# dc26-dev-board.net
KiCad netlist of a schematic drawn in EAGLE
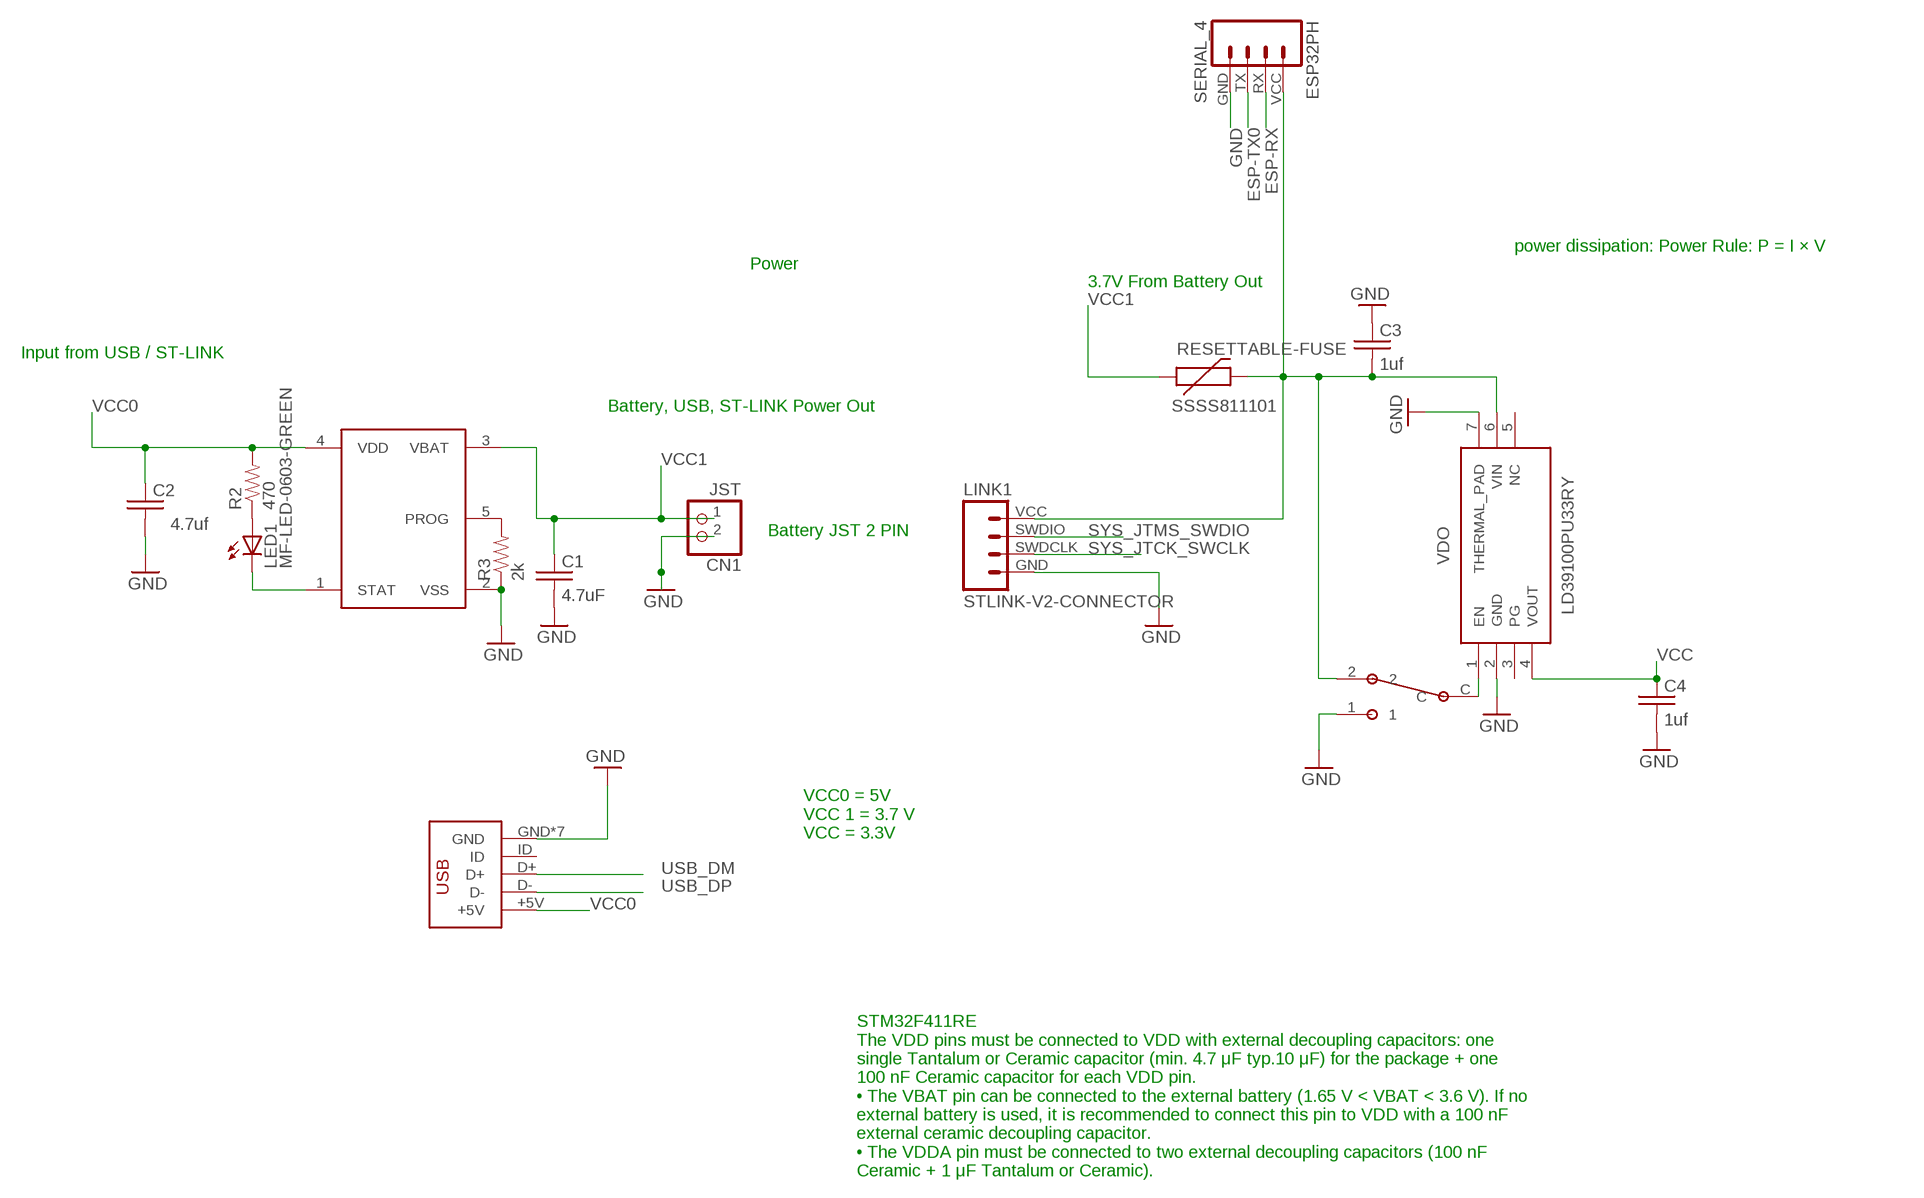
[diagram p0: schematic, sheet 1]
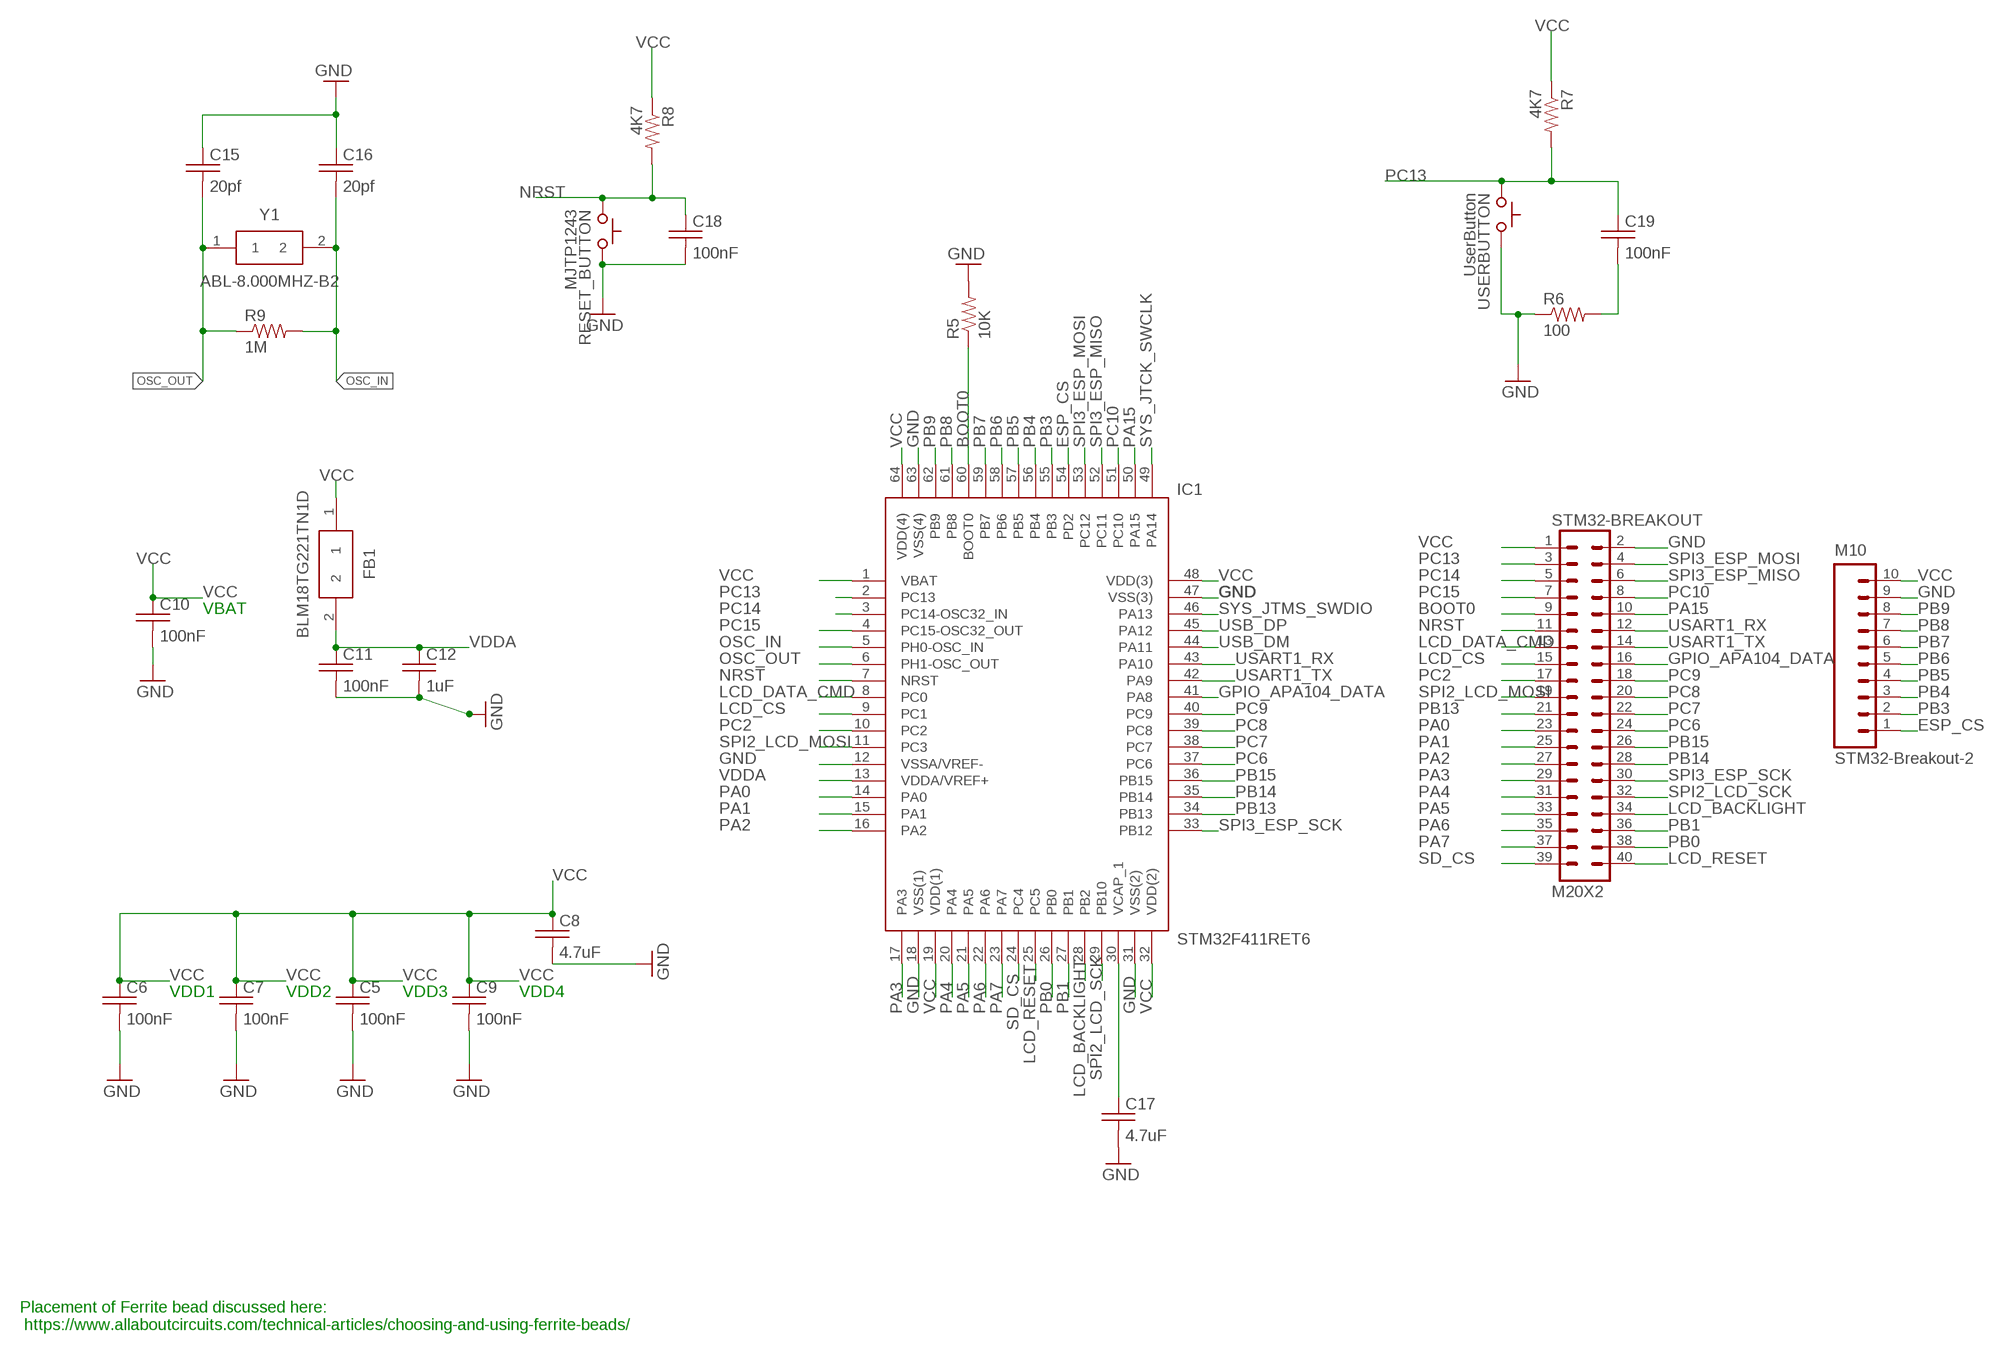
[diagram p1: schematic, sheet 2]
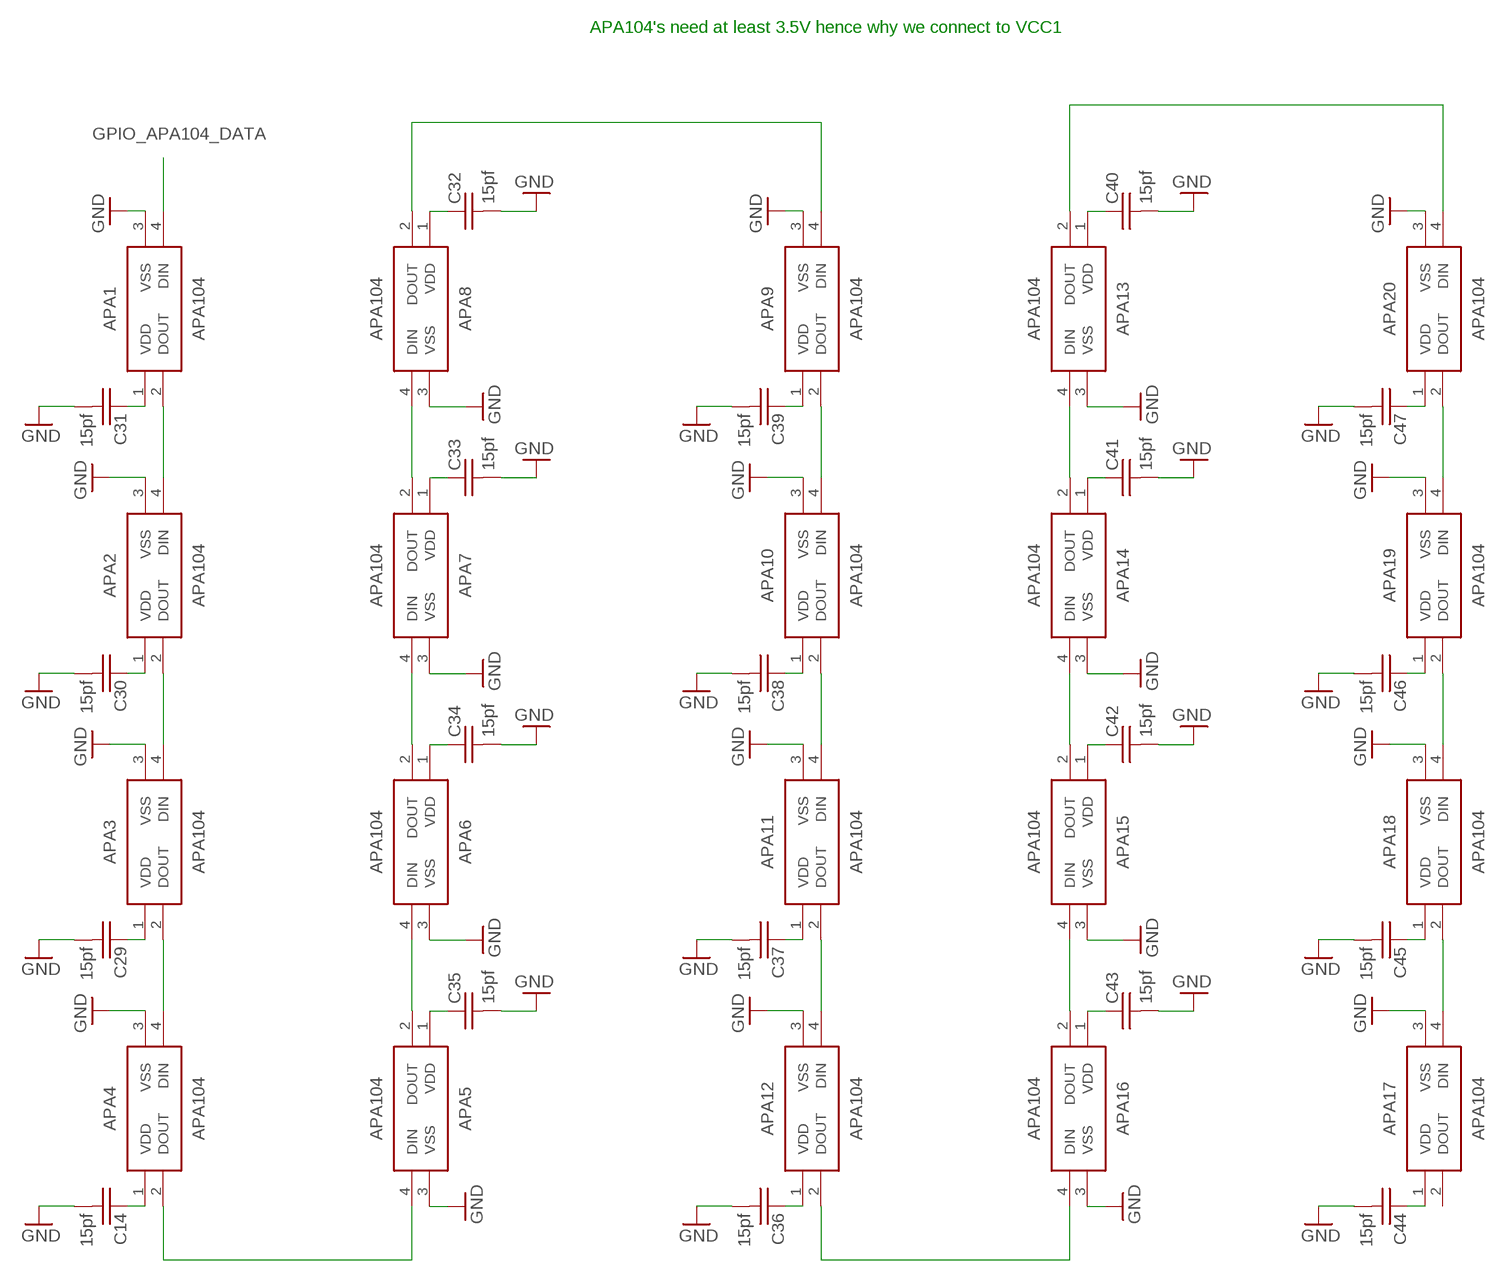
[diagram p2: schematic, sheet 3]
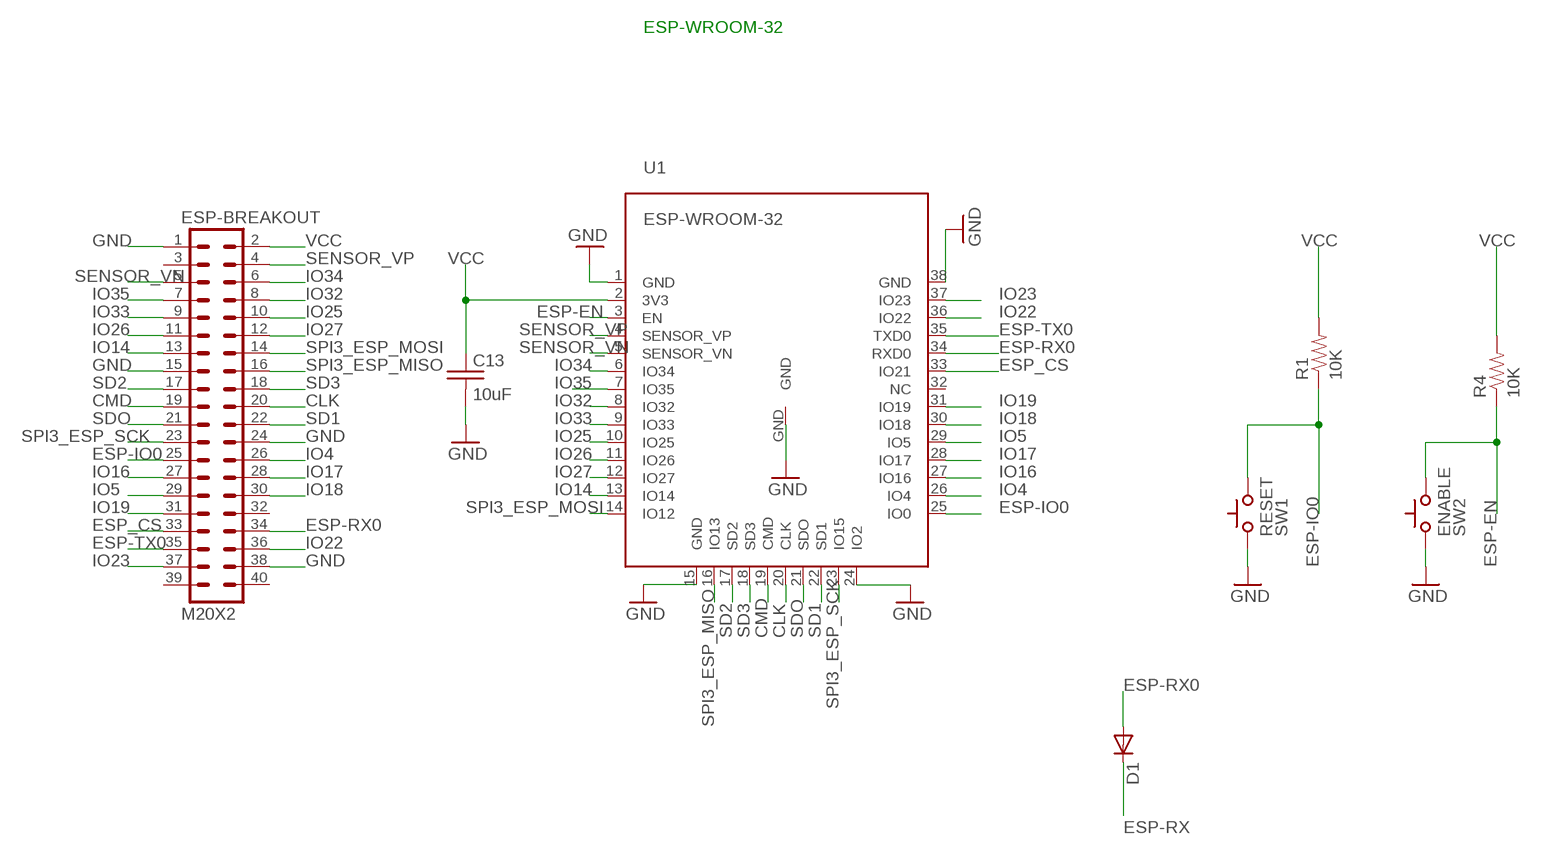
[diagram p3: schematic, sheet 4]
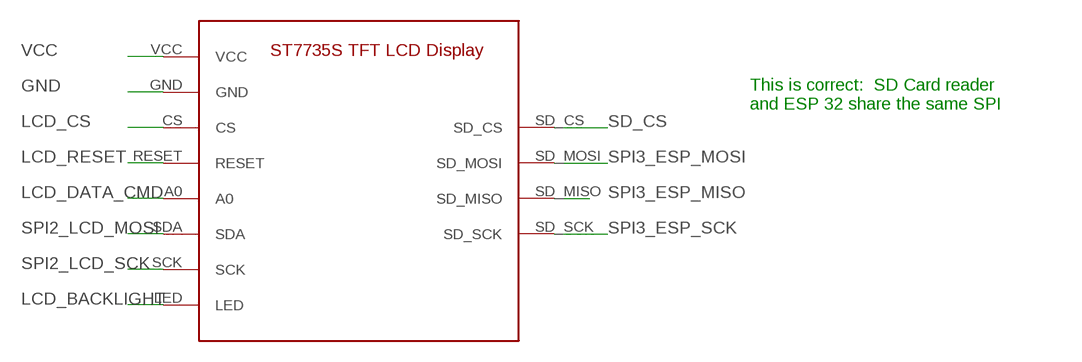
[diagram p4: schematic, sheet 5]
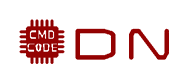
[diagram p5: schematic, sheet 6]
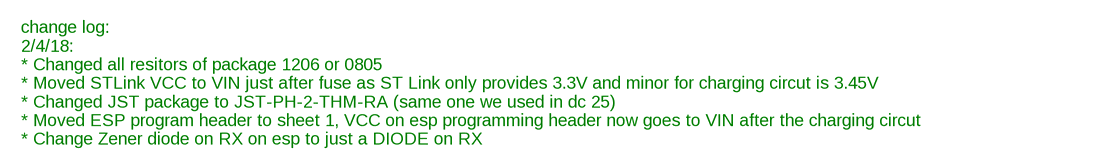
[diagram p6: schematic, sheet 7]

(export (version "E")
  (design (tool "Eeschema 10.0.6"))
  (components
    (comp (ref "C5")
      (value "100nF")
      (footprint "eagle-import:C0805")
      (libsource (lib "eagle-import") (part "C-USC0805"))
    )
    (comp (ref "C6")
      (value "100nF")
      (footprint "eagle-import:C0805")
      (libsource (lib "eagle-import") (part "C-USC0805"))
    )
    (comp (ref "C7")
      (value "100nF")
      (footprint "eagle-import:C0805")
      (libsource (lib "eagle-import") (part "C-USC0805"))
    )
    (comp (ref "C8")
      (value "4.7uF")
      (footprint "eagle-import:C0805")
      (libsource (lib "eagle-import") (part "C-USC0805"))
    )
    (comp (ref "C9")
      (value "100nF")
      (footprint "eagle-import:C0805")
      (libsource (lib "eagle-import") (part "C-USC0805"))
    )
    (comp (ref "C10")
      (value "100nF")
      (footprint "eagle-import:C0805")
      (libsource (lib "eagle-import") (part "C-USC0805"))
    )
    (comp (ref "C11")
      (value "100nF")
      (footprint "eagle-import:C0805")
      (libsource (lib "eagle-import") (part "C-USC0805"))
    )
    (comp (ref "C12")
      (value "1uF")
      (footprint "eagle-import:C0805")
      (libsource (lib "eagle-import") (part "C-USC0805"))
    )
    (comp (ref "C15")
      (value "20pf")
      (footprint "eagle-import:C0805")
      (libsource (lib "eagle-import") (part "C-USC0805"))
    )
    (comp (ref "C16")
      (value "20pf")
      (footprint "eagle-import:C0805")
      (libsource (lib "eagle-import") (part "C-USC0805"))
    )
    (comp (ref "C17")
      (value "4.7uF")
      (footprint "eagle-import:C0805")
      (libsource (lib "eagle-import") (part "C-USC0805"))
    )
    (comp (ref "C18")
      (value "100nF")
      (footprint "eagle-import:C0805")
      (libsource (lib "eagle-import") (part "C-USC0805"))
    )
    (comp (ref "C19")
      (value "100nF")
      (footprint "eagle-import:C0805")
      (libsource (lib "eagle-import") (part "C-USC0805"))
    )
    (comp (ref "FB1")
      (value "BLM18TG221TN1D")
      (footprint "eagle-import:BEADC1608X75N")
      (fields (field (name "RS_PART_NUMBER") "6197526"))
      (libsource (lib "eagle-import") (part "BLM18TG221TN1D"))
    )
    (comp (ref "IC1")
      (value "STM32F411RET6")
      (footprint "eagle-import:QFP50P1200X1200X160-64N")
      (fields (field (name "RS_PART_NUMBER") "1106617P"))
      (libsource (lib "eagle-import") (part "STM32F411RET6"))
    )
    (comp (ref "M10")
      (value "STM32-Breakout-2")
      (footprint "eagle-import:1X10")
      (libsource (lib "eagle-import") (part "M10SILK_FEMALE_PTH"))
    )
    (comp (ref "R5")
      (value "10K")
      (footprint "eagle-import:0805")
      (libsource (lib "eagle-import") (part "RESISTOR0805-RES"))
    )
    (comp (ref "R6")
      (value "100")
      (footprint "eagle-import:0805")
      (libsource (lib "eagle-import") (part "RESISTOR0805-RES"))
    )
    (comp (ref "R7")
      (value "4K7")
      (footprint "eagle-import:0805")
      (libsource (lib "eagle-import") (part "RESISTOR0805-RES"))
    )
    (comp (ref "R8")
      (value "4K7")
      (footprint "eagle-import:0805")
      (libsource (lib "eagle-import") (part "RESISTOR0805-RES"))
    )
    (comp (ref "R9")
      (value "1M")
      (footprint "eagle-import:0805")
      (libsource (lib "eagle-import") (part "RESISTOR0805-RES"))
    )
    (comp (ref "RESET_BUTTON")
      (value "MJTP1243")
      (footprint "eagle-import:TACTILE-2PIN-NARROW")
      (libsource (lib "eagle-import") (part "SWITCH_TACTILETACTILE-2PIN-NARROW"))
    )
    (comp (ref "STM32-BREAKOUT")
      (value "M20X2")
      (footprint "eagle-import:2X20")
      (libsource (lib "eagle-import") (part "M20X2"))
    )
    (comp (ref "USERBUTTON")
      (value "UserButton")
      (footprint "eagle-import:TACTILE-2PIN-NARROW")
      (libsource (lib "eagle-import") (part "SWITCH_TACTILETACTILE-2PIN-NARROW"))
    )
    (comp (ref "Y1")
      (value "ABL-8.000MHZ-B2")
      (footprint "eagle-import:HC_49US_(AT49)PTH")
      (libsource (lib "eagle-import") (part "ABL-8.000MHZ-B2"))
    )
    (comp (ref "C13")
      (value "10uF")
      (footprint "eagle-import:C0805")
      (libsource (lib "eagle-import") (part "C-USC0805"))
    )
    (comp (ref "D1")
      (value "DIODESOD")
      (footprint "eagle-import:SOD-323")
      (libsource (lib "eagle-import") (part "DIODESOD"))
    )
    (comp (ref "ENABLE")
      (value "SW2")
      (footprint "eagle-import:TACTILE-2PIN-NARROW")
      (libsource (lib "eagle-import") (part "SWITCH_TACTILETACTILE-2PIN-NARROW"))
    )
    (comp (ref "ESP-BREAKOUT")
      (value "M20X2")
      (footprint "eagle-import:2X20")
      (libsource (lib "eagle-import") (part "M20X2"))
    )
    (comp (ref "R1")
      (value "10K")
      (footprint "eagle-import:0805")
      (libsource (lib "eagle-import") (part "RESISTOR0805-RES"))
    )
    (comp (ref "R4")
      (value "10K")
      (footprint "eagle-import:0805")
      (libsource (lib "eagle-import") (part "RESISTOR0805-RES"))
    )
    (comp (ref "RESET")
      (value "SW1")
      (footprint "eagle-import:TACTILE-2PIN-NARROW")
      (libsource (lib "eagle-import") (part "SWITCH_TACTILETACTILE-2PIN-NARROW"))
    )
    (comp (ref "U1")
      (value "ESP-WROOM-32")
      (footprint "eagle-import:ESP-WROOM-32")
      (libsource (lib "eagle-import") (part "ESP-WROOM-32"))
    )
    (comp (ref "C1")
      (value "4.7uF")
      (footprint "eagle-import:C0805")
      (libsource (lib "eagle-import") (part "C-USC0805"))
    )
    (comp (ref "C2")
      (value "4.7uf")
      (footprint "eagle-import:C0805")
      (libsource (lib "eagle-import") (part "C-USC0805"))
    )
    (comp (ref "C3")
      (value "1uf")
      (footprint "eagle-import:C0805")
      (libsource (lib "eagle-import") (part "C-USC0805"))
    )
    (comp (ref "C4")
      (value "1uf")
      (footprint "eagle-import:C0805")
      (libsource (lib "eagle-import") (part "C-USC0805"))
    )
    (comp (ref "CHARGING_CIRCUT")
      (value "MCP73831")
      (footprint "eagle-import:SOT23-5")
      (libsource (lib "eagle-import") (part "DS21984E"))
    )
    (comp (ref "CN1")
      (value "JST")
      (footprint "eagle-import:JST-PH-2-THM-RA")
      (libsource (lib "eagle-import") (part "JST_2PIN-THM-RA"))
    )
    (comp (ref "ESP32PH")
      (value "SERIAL_4")
      (footprint "eagle-import:SERIAL_HEADER_4")
      (libsource (lib "eagle-import") (part "SERIAL_4"))
    )
    (comp (ref "LED1")
      (value "MF-LED-0603-GREEN")
      (footprint "eagle-import:LED-1206")
      (libsource (lib "eagle-import") (part "LED1206"))
    )
    (comp (ref "LINK1")
      (value "STLINK-V2-CONNECTOR")
      (footprint "eagle-import:1X04")
      (libsource (lib "eagle-import") (part "STLINK-V2-CONNECTOR"))
    )
    (comp (ref "P1")
      (value "SSSS811101")
      (footprint "eagle-import:SPDT_SSAJ120100")
      (libsource (lib "eagle-import") (part "SWITCH_SPDT"))
    )
    (comp (ref "R2")
      (value "470")
      (footprint "eagle-import:0805")
      (libsource (lib "eagle-import") (part "RESISTOR0805-RES"))
    )
    (comp (ref "R3")
      (value "2k")
      (footprint "eagle-import:0805")
      (libsource (lib "eagle-import") (part "RESISTOR0805-RES"))
    )
    (comp (ref "RESETTABLE-FUSE")
      (value "SSSS811101")
      (footprint "eagle-import:PTC-1206")
      (libsource (lib "eagle-import") (part "PTCSMD"))
    )
    (comp (ref "USB")
      (value "DX4R005JJ2DX4R005JJ2")
      (footprint "eagle-import:DX4R005JJ2")
      (libsource (lib "eagle-import") (part "DX4R005JJ2DX4R005JJ2"))
    )
    (comp (ref "VDO")
      (value "LD39100PU33RY")
      (footprint "eagle-import:SON95P300X300X90-7N")
      (libsource (lib "eagle-import") (part "LD39100PU33RY"))
    )
    (comp (ref "U$1")
      (value "ST7735S_LCD_MODULE")
      (footprint "eagle-import:ST7735S_LCD_DISPLAY")
      (libsource (lib "eagle-import") (part "ST7735S_LCD_MODULE"))
    )
    (comp (ref "U$2")
      (value "CMD_C0DE_LOGO")
      (footprint "eagle-import:CMD_C0DE_LOGO")
      (libsource (lib "eagle-import") (part "CMD_C0DE_LOGO"))
    )
    (comp (ref "U$3")
      (value "DARKNET_DD")
      (footprint "eagle-import:DARKNET_D")
      (libsource (lib "eagle-import") (part "DARKNET_DD"))
    )
    (comp (ref "U$4")
      (value "DARKNET_NN")
      (footprint "eagle-import:DARKNET_N")
      (libsource (lib "eagle-import") (part "DARKNET_NN"))
    )
    (comp (ref "APA1")
      (value "APA104")
      (footprint "eagle-import:APA104")
      (libsource (lib "eagle-import") (part "APA104"))
    )
    (comp (ref "APA2")
      (value "APA104")
      (footprint "eagle-import:APA104")
      (libsource (lib "eagle-import") (part "APA104"))
    )
    (comp (ref "APA3")
      (value "APA104")
      (footprint "eagle-import:APA104")
      (libsource (lib "eagle-import") (part "APA104"))
    )
    (comp (ref "APA4")
      (value "APA104")
      (footprint "eagle-import:APA104")
      (libsource (lib "eagle-import") (part "APA104"))
    )
    (comp (ref "APA5")
      (value "APA104")
      (footprint "eagle-import:APA104")
      (libsource (lib "eagle-import") (part "APA104"))
    )
    (comp (ref "APA6")
      (value "APA104")
      (footprint "eagle-import:APA104")
      (libsource (lib "eagle-import") (part "APA104"))
    )
    (comp (ref "APA7")
      (value "APA104")
      (footprint "eagle-import:APA104")
      (libsource (lib "eagle-import") (part "APA104"))
    )
    (comp (ref "APA8")
      (value "APA104")
      (footprint "eagle-import:APA104")
      (libsource (lib "eagle-import") (part "APA104"))
    )
    (comp (ref "APA9")
      (value "APA104")
      (footprint "eagle-import:APA104")
      (libsource (lib "eagle-import") (part "APA104"))
    )
    (comp (ref "APA10")
      (value "APA104")
      (footprint "eagle-import:APA104")
      (libsource (lib "eagle-import") (part "APA104"))
    )
    (comp (ref "APA11")
      (value "APA104")
      (footprint "eagle-import:APA104")
      (libsource (lib "eagle-import") (part "APA104"))
    )
    (comp (ref "APA12")
      (value "APA104")
      (footprint "eagle-import:APA104")
      (libsource (lib "eagle-import") (part "APA104"))
    )
    (comp (ref "APA13")
      (value "APA104")
      (footprint "eagle-import:APA104")
      (libsource (lib "eagle-import") (part "APA104"))
    )
    (comp (ref "APA14")
      (value "APA104")
      (footprint "eagle-import:APA104")
      (libsource (lib "eagle-import") (part "APA104"))
    )
    (comp (ref "APA15")
      (value "APA104")
      (footprint "eagle-import:APA104")
      (libsource (lib "eagle-import") (part "APA104"))
    )
    (comp (ref "APA16")
      (value "APA104")
      (footprint "eagle-import:APA104")
      (libsource (lib "eagle-import") (part "APA104"))
    )
    (comp (ref "APA17")
      (value "APA104")
      (footprint "eagle-import:APA104")
      (libsource (lib "eagle-import") (part "APA104"))
    )
    (comp (ref "APA18")
      (value "APA104")
      (footprint "eagle-import:APA104")
      (libsource (lib "eagle-import") (part "APA104"))
    )
    (comp (ref "APA19")
      (value "APA104")
      (footprint "eagle-import:APA104")
      (libsource (lib "eagle-import") (part "APA104"))
    )
    (comp (ref "APA20")
      (value "APA104")
      (footprint "eagle-import:APA104")
      (libsource (lib "eagle-import") (part "APA104"))
    )
    (comp (ref "C14")
      (value "15pf")
      (footprint "eagle-import:C0805")
      (libsource (lib "eagle-import") (part "C-USC0805"))
    )
    (comp (ref "C29")
      (value "15pf")
      (footprint "eagle-import:C0805")
      (libsource (lib "eagle-import") (part "C-USC0805"))
    )
    (comp (ref "C30")
      (value "15pf")
      (footprint "eagle-import:C0805")
      (libsource (lib "eagle-import") (part "C-USC0805"))
    )
    (comp (ref "C31")
      (value "15pf")
      (footprint "eagle-import:C0805")
      (libsource (lib "eagle-import") (part "C-USC0805"))
    )
    (comp (ref "C32")
      (value "15pf")
      (footprint "eagle-import:C0805")
      (libsource (lib "eagle-import") (part "C-USC0805"))
    )
    (comp (ref "C33")
      (value "15pf")
      (footprint "eagle-import:C0805")
      (libsource (lib "eagle-import") (part "C-USC0805"))
    )
    (comp (ref "C34")
      (value "15pf")
      (footprint "eagle-import:C0805")
      (libsource (lib "eagle-import") (part "C-USC0805"))
    )
    (comp (ref "C35")
      (value "15pf")
      (footprint "eagle-import:C0805")
      (libsource (lib "eagle-import") (part "C-USC0805"))
    )
    (comp (ref "C36")
      (value "15pf")
      (footprint "eagle-import:C0805")
      (libsource (lib "eagle-import") (part "C-USC0805"))
    )
    (comp (ref "C37")
      (value "15pf")
      (footprint "eagle-import:C0805")
      (libsource (lib "eagle-import") (part "C-USC0805"))
    )
    (comp (ref "C38")
      (value "15pf")
      (footprint "eagle-import:C0805")
      (libsource (lib "eagle-import") (part "C-USC0805"))
    )
    (comp (ref "C39")
      (value "15pf")
      (footprint "eagle-import:C0805")
      (libsource (lib "eagle-import") (part "C-USC0805"))
    )
    (comp (ref "C40")
      (value "15pf")
      (footprint "eagle-import:C0805")
      (libsource (lib "eagle-import") (part "C-USC0805"))
    )
    (comp (ref "C41")
      (value "15pf")
      (footprint "eagle-import:C0805")
      (libsource (lib "eagle-import") (part "C-USC0805"))
    )
    (comp (ref "C42")
      (value "15pf")
      (footprint "eagle-import:C0805")
      (libsource (lib "eagle-import") (part "C-USC0805"))
    )
    (comp (ref "C43")
      (value "15pf")
      (footprint "eagle-import:C0805")
      (libsource (lib "eagle-import") (part "C-USC0805"))
    )
    (comp (ref "C44")
      (value "15pf")
      (footprint "eagle-import:C0805")
      (libsource (lib "eagle-import") (part "C-USC0805"))
    )
    (comp (ref "C45")
      (value "15pf")
      (footprint "eagle-import:C0805")
      (libsource (lib "eagle-import") (part "C-USC0805"))
    )
    (comp (ref "C46")
      (value "15pf")
      (footprint "eagle-import:C0805")
      (libsource (lib "eagle-import") (part "C-USC0805"))
    )
    (comp (ref "C47")
      (value "15pf")
      (footprint "eagle-import:C0805")
      (libsource (lib "eagle-import") (part "C-USC0805"))
    )
  )
  (nets
    (net (code "1") (name "BOOT0") (class "Default")
      (node (ref "IC1") (pin "60") (pinfunction "BOOT0_60") (pintype "passive"))
      (node (ref "R5") (pin "1") (pinfunction "1_1") (pintype "passive"))
      (node (ref "STM32-BREAKOUT") (pin "9") (pinfunction "9_9") (pintype "passive"))
    )
    (net (code "2") (name "CLK") (class "Default")
      (node (ref "ESP-BREAKOUT") (pin "20") (pinfunction "20_20") (pintype "passive"))
      (node (ref "U1") (pin "20") (pinfunction "CLK_20") (pintype "bidirectional"))
    )
    (net (code "3") (name "CMD") (class "Default")
      (node (ref "ESP-BREAKOUT") (pin "19") (pinfunction "19_19") (pintype "passive"))
      (node (ref "U1") (pin "19") (pinfunction "CMD_19") (pintype "bidirectional"))
    )
    (net (code "4") (name "ESP-EN") (class "Default")
      (node (ref "ENABLE") (pin "P$1") (pinfunction "A_P$1") (pintype "passive"))
      (node (ref "R4") (pin "1") (pinfunction "1_1") (pintype "passive"))
      (node (ref "U1") (pin "3") (pinfunction "EN_3") (pintype "bidirectional"))
    )
    (net (code "5") (name "ESP-IO0") (class "Default")
      (node (ref "ESP-BREAKOUT") (pin "25") (pinfunction "25_25") (pintype "passive"))
      (node (ref "R1") (pin "1") (pinfunction "1_1") (pintype "passive"))
      (node (ref "RESET") (pin "P$1") (pinfunction "A_P$1") (pintype "passive"))
      (node (ref "U1") (pin "25") (pinfunction "IO0_25") (pintype "bidirectional"))
    )
    (net (code "6") (name "ESP-RX") (class "Default")
      (node (ref "D1") (pin "1") (pinfunction "C_1") (pintype "passive"))
      (node (ref "ESP32PH") (pin "RX") (pinfunction "RX_RX") (pintype "bidirectional"))
    )
    (net (code "7") (name "ESP-RX0") (class "Default")
      (node (ref "D1") (pin "2") (pinfunction "A_2") (pintype "passive"))
      (node (ref "ESP-BREAKOUT") (pin "34") (pinfunction "34_34") (pintype "passive"))
      (node (ref "U1") (pin "34") (pinfunction "RXD0_34") (pintype "bidirectional"))
    )
    (net (code "8") (name "ESP-TX0") (class "Default")
      (node (ref "ESP-BREAKOUT") (pin "35") (pinfunction "35_35") (pintype "passive"))
      (node (ref "ESP32PH") (pin "TX") (pinfunction "TX_TX") (pintype "input"))
      (node (ref "U1") (pin "35") (pinfunction "TXD0_35") (pintype "bidirectional"))
    )
    (net (code "9") (name "ESP_CS") (class "Default")
      (node (ref "ESP-BREAKOUT") (pin "33") (pinfunction "33_33") (pintype "passive"))
      (node (ref "IC1") (pin "54") (pinfunction "PD2_54") (pintype "passive"))
      (node (ref "M10") (pin "1") (pinfunction "1_1") (pintype "passive"))
      (node (ref "U1") (pin "33") (pinfunction "IO21_33") (pintype "bidirectional"))
    )
    (net (code "10") (name "GND") (class "Default")
      (node (ref "APA1") (pin "3") (pinfunction "VSS_3") (pintype "power_in"))
      (node (ref "APA10") (pin "3") (pinfunction "VSS_3") (pintype "power_in"))
      (node (ref "APA11") (pin "3") (pinfunction "VSS_3") (pintype "power_in"))
      (node (ref "APA12") (pin "3") (pinfunction "VSS_3") (pintype "power_in"))
      (node (ref "APA13") (pin "3") (pinfunction "VSS_3") (pintype "power_in"))
      (node (ref "APA14") (pin "3") (pinfunction "VSS_3") (pintype "power_in"))
      (node (ref "APA15") (pin "3") (pinfunction "VSS_3") (pintype "power_in"))
      (node (ref "APA16") (pin "3") (pinfunction "VSS_3") (pintype "power_in"))
      (node (ref "APA17") (pin "3") (pinfunction "VSS_3") (pintype "power_in"))
      (node (ref "APA18") (pin "3") (pinfunction "VSS_3") (pintype "power_in"))
      (node (ref "APA19") (pin "3") (pinfunction "VSS_3") (pintype "power_in"))
      (node (ref "APA2") (pin "3") (pinfunction "VSS_3") (pintype "power_in"))
      (node (ref "APA20") (pin "3") (pinfunction "VSS_3") (pintype "power_in"))
      (node (ref "APA3") (pin "3") (pinfunction "VSS_3") (pintype "power_in"))
      (node (ref "APA4") (pin "3") (pinfunction "VSS_3") (pintype "power_in"))
      (node (ref "APA5") (pin "3") (pinfunction "VSS_3") (pintype "power_in"))
      (node (ref "APA6") (pin "3") (pinfunction "VSS_3") (pintype "power_in"))
      (node (ref "APA7") (pin "3") (pinfunction "VSS_3") (pintype "power_in"))
      (node (ref "APA8") (pin "3") (pinfunction "VSS_3") (pintype "power_in"))
      (node (ref "APA9") (pin "3") (pinfunction "VSS_3") (pintype "power_in"))
      (node (ref "C1") (pin "2") (pinfunction "2_2") (pintype "passive"))
      (node (ref "C10") (pin "2") (pinfunction "2_2") (pintype "passive"))
      (node (ref "C11") (pin "2") (pinfunction "2_2") (pintype "passive"))
      (node (ref "C12") (pin "2") (pinfunction "2_2") (pintype "passive"))
      (node (ref "C13") (pin "2") (pinfunction "2_2") (pintype "passive"))
      (node (ref "C14") (pin "2") (pinfunction "2_2") (pintype "passive"))
      (node (ref "C15") (pin "1") (pinfunction "1_1") (pintype "passive"))
      (node (ref "C16") (pin "1") (pinfunction "1_1") (pintype "passive"))
      (node (ref "C17") (pin "2") (pinfunction "2_2") (pintype "passive"))
      (node (ref "C18") (pin "2") (pinfunction "2_2") (pintype "passive"))
      (node (ref "C2") (pin "2") (pinfunction "2_2") (pintype "passive"))
      (node (ref "C29") (pin "2") (pinfunction "2_2") (pintype "passive"))
      (node (ref "C3") (pin "1") (pinfunction "1_1") (pintype "passive"))
      (node (ref "C30") (pin "2") (pinfunction "2_2") (pintype "passive"))
      (node (ref "C31") (pin "2") (pinfunction "2_2") (pintype "passive"))
      (node (ref "C32") (pin "2") (pinfunction "2_2") (pintype "passive"))
      (node (ref "C33") (pin "2") (pinfunction "2_2") (pintype "passive"))
      (node (ref "C34") (pin "2") (pinfunction "2_2") (pintype "passive"))
      (node (ref "C35") (pin "2") (pinfunction "2_2") (pintype "passive"))
      (node (ref "C36") (pin "2") (pinfunction "2_2") (pintype "passive"))
      (node (ref "C37") (pin "2") (pinfunction "2_2") (pintype "passive"))
      (node (ref "C38") (pin "2") (pinfunction "2_2") (pintype "passive"))
      (node (ref "C39") (pin "2") (pinfunction "2_2") (pintype "passive"))
      (node (ref "C4") (pin "2") (pinfunction "2_2") (pintype "passive"))
      (node (ref "C40") (pin "2") (pinfunction "2_2") (pintype "passive"))
      (node (ref "C41") (pin "2") (pinfunction "2_2") (pintype "passive"))
      (node (ref "C42") (pin "2") (pinfunction "2_2") (pintype "passive"))
      (node (ref "C43") (pin "2") (pinfunction "2_2") (pintype "passive"))
      (node (ref "C44") (pin "2") (pinfunction "2_2") (pintype "passive"))
      (node (ref "C45") (pin "2") (pinfunction "2_2") (pintype "passive"))
      (node (ref "C46") (pin "2") (pinfunction "2_2") (pintype "passive"))
      (node (ref "C47") (pin "2") (pinfunction "2_2") (pintype "passive"))
      (node (ref "C5") (pin "2") (pinfunction "2_2") (pintype "passive"))
      (node (ref "C6") (pin "2") (pinfunction "2_2") (pintype "passive"))
      (node (ref "C7") (pin "2") (pinfunction "2_2") (pintype "passive"))
      (node (ref "C8") (pin "2") (pinfunction "2_2") (pintype "passive"))
      (node (ref "C9") (pin "2") (pinfunction "2_2") (pintype "passive"))
      (node (ref "CHARGING_CIRCUT") (pin "2") (pinfunction "VSS_2") (pintype "bidirectional"))
      (node (ref "CN1") (pin "2") (pinfunction "1_2") (pintype "passive"))
      (node (ref "ENABLE") (pin "P$2") (pinfunction "C_P$2") (pintype "passive"))
      (node (ref "ESP-BREAKOUT") (pin "1") (pinfunction "1_1") (pintype "passive"))
      (node (ref "ESP-BREAKOUT") (pin "15") (pinfunction "15_15") (pintype "passive"))
      (node (ref "ESP-BREAKOUT") (pin "24") (pinfunction "24_24") (pintype "passive"))
      (node (ref "ESP-BREAKOUT") (pin "38") (pinfunction "38_38") (pintype "passive"))
      (node (ref "ESP32PH") (pin "GND") (pinfunction "GND_GND") (pintype "power_in"))
      (node (ref "IC1") (pin "12") (pinfunction "VSSA/VREF-_12") (pintype "passive"))
      (node (ref "IC1") (pin "18") (pinfunction "VSS(1)_18") (pintype "passive"))
      (node (ref "IC1") (pin "31") (pinfunction "VSS(2)_31") (pintype "passive"))
      (node (ref "IC1") (pin "47") (pinfunction "VSS(3)_47") (pintype "passive"))
      (node (ref "IC1") (pin "63") (pinfunction "VSS(4)_63") (pintype "passive"))
      (node (ref "LINK1") (pin "GND") (pinfunction "GND_GND") (pintype "power_in"))
      (node (ref "M10") (pin "9") (pinfunction "9_9") (pintype "passive"))
      (node (ref "P1") (pin "1") (pinfunction "1_1") (pintype "bidirectional"))
      (node (ref "R3") (pin "1") (pinfunction "1_1") (pintype "passive"))
      (node (ref "R5") (pin "2") (pinfunction "2_2") (pintype "passive"))
      (node (ref "R6") (pin "1") (pinfunction "1_1") (pintype "passive"))
      (node (ref "RESET") (pin "P$2") (pinfunction "C_P$2") (pintype "passive"))
      (node (ref "RESET_BUTTON") (pin "P$1") (pinfunction "A_P$1") (pintype "passive"))
      (node (ref "STM32-BREAKOUT") (pin "2") (pinfunction "2_2") (pintype "passive"))
      (node (ref "U$1") (pin "GND") (pinfunction "GND_GND") (pintype "bidirectional"))
      (node (ref "U1") (pin "1") (pinfunction "GND_1") (pintype "bidirectional"))
      (node (ref "U1") (pin "15") (pinfunction "GND_15") (pintype "bidirectional"))
      (node (ref "U1") (pin "24") (pinfunction "IO2_24") (pintype "bidirectional"))
      (node (ref "U1") (pin "38") (pinfunction "GND_38") (pintype "bidirectional"))
      (node (ref "U1") (pin "GND") (pinfunction "GND_GND") (pintype "bidirectional"))
      (node (ref "USB") (pin "GND") (pinfunction "GND_GND") (pintype "bidirectional"))
      (node (ref "USB") (pin "P$10") (pinfunction "GND_P$10") (pintype "bidirectional"))
      (node (ref "USB") (pin "P$11") (pinfunction "GND_P$11") (pintype "bidirectional"))
      (node (ref "USB") (pin "P$6") (pinfunction "GND_P$6") (pintype "bidirectional"))
      (node (ref "USB") (pin "P$7") (pinfunction "GND_P$7") (pintype "bidirectional"))
      (node (ref "USB") (pin "P$8") (pinfunction "GND_P$8") (pintype "bidirectional"))
      (node (ref "USB") (pin "P$9") (pinfunction "GND_P$9") (pintype "bidirectional"))
      (node (ref "USERBUTTON") (pin "P$1") (pinfunction "A_P$1") (pintype "passive"))
      (node (ref "VDO") (pin "2") (pinfunction "GND_2") (pintype "passive"))
      (node (ref "VDO") (pin "7") (pinfunction "THERMAL_PAD_7") (pintype "passive"))
    )
    (net (code "11") (name "GPIO_APA104_DATA") (class "Default")
      (node (ref "APA1") (pin "4") (pinfunction "DIN_4") (pintype "input"))
      (node (ref "IC1") (pin "41") (pinfunction "PA8_41") (pintype "passive"))
      (node (ref "STM32-BREAKOUT") (pin "16") (pinfunction "16_16") (pintype "passive"))
    )
    (net (code "12") (name "IO4") (class "Default")
      (node (ref "ESP-BREAKOUT") (pin "26") (pinfunction "26_26") (pintype "passive"))
      (node (ref "U1") (pin "26") (pinfunction "IO4_26") (pintype "bidirectional"))
    )
    (net (code "13") (name "IO5") (class "Default")
      (node (ref "ESP-BREAKOUT") (pin "29") (pinfunction "29_29") (pintype "passive"))
      (node (ref "U1") (pin "29") (pinfunction "IO5_29") (pintype "bidirectional"))
    )
    (net (code "14") (name "IO14") (class "Default")
      (node (ref "ESP-BREAKOUT") (pin "13") (pinfunction "13_13") (pintype "passive"))
      (node (ref "U1") (pin "13") (pinfunction "IO14_13") (pintype "bidirectional"))
    )
    (net (code "15") (name "IO16") (class "Default")
      (node (ref "ESP-BREAKOUT") (pin "27") (pinfunction "27_27") (pintype "passive"))
      (node (ref "U1") (pin "27") (pinfunction "IO16_27") (pintype "bidirectional"))
    )
    (net (code "16") (name "IO17") (class "Default")
      (node (ref "ESP-BREAKOUT") (pin "28") (pinfunction "28_28") (pintype "passive"))
      (node (ref "U1") (pin "28") (pinfunction "IO17_28") (pintype "bidirectional"))
    )
    (net (code "17") (name "IO18") (class "Default")
      (node (ref "ESP-BREAKOUT") (pin "30") (pinfunction "30_30") (pintype "passive"))
      (node (ref "U1") (pin "30") (pinfunction "IO18_30") (pintype "bidirectional"))
    )
    (net (code "18") (name "IO19") (class "Default")
      (node (ref "ESP-BREAKOUT") (pin "31") (pinfunction "31_31") (pintype "passive"))
      (node (ref "U1") (pin "31") (pinfunction "IO19_31") (pintype "bidirectional"))
    )
    (net (code "19") (name "IO22") (class "Default")
      (node (ref "ESP-BREAKOUT") (pin "36") (pinfunction "36_36") (pintype "passive"))
      (node (ref "U1") (pin "36") (pinfunction "IO22_36") (pintype "bidirectional"))
    )
    (net (code "20") (name "IO23") (class "Default")
      (node (ref "ESP-BREAKOUT") (pin "37") (pinfunction "37_37") (pintype "passive"))
      (node (ref "U1") (pin "37") (pinfunction "IO23_37") (pintype "bidirectional"))
    )
    (net (code "21") (name "IO25") (class "Default")
      (node (ref "ESP-BREAKOUT") (pin "10") (pinfunction "10_10") (pintype "passive"))
      (node (ref "U1") (pin "10") (pinfunction "IO25_10") (pintype "bidirectional"))
    )
    (net (code "22") (name "IO26") (class "Default")
      (node (ref "ESP-BREAKOUT") (pin "11") (pinfunction "11_11") (pintype "passive"))
      (node (ref "U1") (pin "11") (pinfunction "IO26_11") (pintype "bidirectional"))
    )
    (net (code "23") (name "IO27") (class "Default")
      (node (ref "ESP-BREAKOUT") (pin "12") (pinfunction "12_12") (pintype "passive"))
      (node (ref "U1") (pin "12") (pinfunction "IO27_12") (pintype "bidirectional"))
    )
    (net (code "24") (name "IO32") (class "Default")
      (node (ref "ESP-BREAKOUT") (pin "8") (pinfunction "8_8") (pintype "passive"))
      (node (ref "U1") (pin "8") (pinfunction "IO32_8") (pintype "bidirectional"))
    )
    (net (code "25") (name "IO33") (class "Default")
      (node (ref "ESP-BREAKOUT") (pin "9") (pinfunction "9_9") (pintype "passive"))
      (node (ref "U1") (pin "9") (pinfunction "IO33_9") (pintype "bidirectional"))
    )
    (net (code "26") (name "IO34") (class "Default")
      (node (ref "ESP-BREAKOUT") (pin "6") (pinfunction "6_6") (pintype "passive"))
      (node (ref "U1") (pin "6") (pinfunction "IO34_6") (pintype "bidirectional"))
    )
    (net (code "27") (name "IO35") (class "Default")
      (node (ref "ESP-BREAKOUT") (pin "7") (pinfunction "7_7") (pintype "passive"))
      (node (ref "U1") (pin "7") (pinfunction "IO35_7") (pintype "bidirectional"))
    )
    (net (code "28") (name "LCD_BACKLIGHT") (class "Default")
      (node (ref "IC1") (pin "28") (pinfunction "PB2_28") (pintype "passive"))
      (node (ref "STM32-BREAKOUT") (pin "34") (pinfunction "34_34") (pintype "passive"))
      (node (ref "U$1") (pin "LED") (pinfunction "LED_LED") (pintype "bidirectional"))
    )
    (net (code "29") (name "LCD_CS") (class "Default")
      (node (ref "IC1") (pin "9") (pinfunction "PC1_9") (pintype "passive"))
      (node (ref "STM32-BREAKOUT") (pin "15") (pinfunction "15_15") (pintype "passive"))
      (node (ref "U$1") (pin "CS") (pinfunction "CS_CS") (pintype "bidirectional"))
    )
    (net (code "30") (name "LCD_DATA_CMD") (class "Default")
      (node (ref "IC1") (pin "8") (pinfunction "PC0_8") (pintype "passive"))
      (node (ref "STM32-BREAKOUT") (pin "13") (pinfunction "13_13") (pintype "passive"))
      (node (ref "U$1") (pin "A0") (pinfunction "A0_A0") (pintype "bidirectional"))
    )
    (net (code "31") (name "LCD_RESET") (class "Default")
      (node (ref "IC1") (pin "25") (pinfunction "PC5_25") (pintype "passive"))
      (node (ref "STM32-BREAKOUT") (pin "40") (pinfunction "40_40") (pintype "passive"))
      (node (ref "U$1") (pin "RESET") (pinfunction "RESET_RESET") (pintype "bidirectional"))
    )
    (net (code "32") (name "NRST") (class "Default")
      (node (ref "C18") (pin "1") (pinfunction "1_1") (pintype "passive"))
      (node (ref "IC1") (pin "7") (pinfunction "NRST_7") (pintype "passive"))
      (node (ref "R8") (pin "2") (pinfunction "2_2") (pintype "passive"))
      (node (ref "RESET_BUTTON") (pin "P$2") (pinfunction "C_P$2") (pintype "passive"))
      (node (ref "STM32-BREAKOUT") (pin "11") (pinfunction "11_11") (pintype "passive"))
    )
    (net (code "33") (name "Net-(APA1-DOUT)") (class "Default")
      (node (ref "APA1") (pin "2") (pinfunction "DOUT_2") (pintype "output"))
      (node (ref "APA2") (pin "4") (pinfunction "DIN_4") (pintype "input"))
    )
    (net (code "34") (name "Net-(APA2-DOUT)") (class "Default")
      (node (ref "APA2") (pin "2") (pinfunction "DOUT_2") (pintype "output"))
      (node (ref "APA3") (pin "4") (pinfunction "DIN_4") (pintype "input"))
    )
    (net (code "35") (name "Net-(APA3-DOUT)") (class "Default")
      (node (ref "APA3") (pin "2") (pinfunction "DOUT_2") (pintype "output"))
      (node (ref "APA4") (pin "4") (pinfunction "DIN_4") (pintype "input"))
    )
    (net (code "36") (name "Net-(APA4-DOUT)") (class "Default")
      (node (ref "APA4") (pin "2") (pinfunction "DOUT_2") (pintype "output"))
      (node (ref "APA5") (pin "4") (pinfunction "DIN_4") (pintype "input"))
    )
    (net (code "37") (name "Net-(APA5-DOUT)") (class "Default")
      (node (ref "APA5") (pin "2") (pinfunction "DOUT_2") (pintype "output"))
      (node (ref "APA6") (pin "4") (pinfunction "DIN_4") (pintype "input"))
    )
    (net (code "38") (name "Net-(APA6-DOUT)") (class "Default")
      (node (ref "APA6") (pin "2") (pinfunction "DOUT_2") (pintype "output"))
      (node (ref "APA7") (pin "4") (pinfunction "DIN_4") (pintype "input"))
    )
    (net (code "39") (name "Net-(APA7-DOUT)") (class "Default")
      (node (ref "APA7") (pin "2") (pinfunction "DOUT_2") (pintype "output"))
      (node (ref "APA8") (pin "4") (pinfunction "DIN_4") (pintype "input"))
    )
    (net (code "40") (name "Net-(APA8-DOUT)") (class "Default")
      (node (ref "APA8") (pin "2") (pinfunction "DOUT_2") (pintype "output"))
      (node (ref "APA9") (pin "4") (pinfunction "DIN_4") (pintype "input"))
    )
    (net (code "41") (name "Net-(APA10-DIN)") (class "Default")
      (node (ref "APA10") (pin "4") (pinfunction "DIN_4") (pintype "input"))
      (node (ref "APA9") (pin "2") (pinfunction "DOUT_2") (pintype "output"))
    )
    (net (code "42") (name "Net-(APA10-DOUT)") (class "Default")
      (node (ref "APA10") (pin "2") (pinfunction "DOUT_2") (pintype "output"))
      (node (ref "APA11") (pin "4") (pinfunction "DIN_4") (pintype "input"))
    )
    (net (code "43") (name "Net-(APA11-DOUT)") (class "Default")
      (node (ref "APA11") (pin "2") (pinfunction "DOUT_2") (pintype "output"))
      (node (ref "APA12") (pin "4") (pinfunction "DIN_4") (pintype "input"))
    )
    (net (code "44") (name "Net-(APA12-DOUT)") (class "Default")
      (node (ref "APA12") (pin "2") (pinfunction "DOUT_2") (pintype "output"))
      (node (ref "APA16") (pin "4") (pinfunction "DIN_4") (pintype "input"))
    )
    (net (code "45") (name "Net-(APA13-DIN)") (class "Default")
      (node (ref "APA13") (pin "4") (pinfunction "DIN_4") (pintype "input"))
      (node (ref "APA14") (pin "2") (pinfunction "DOUT_2") (pintype "output"))
    )
    (net (code "46") (name "Net-(APA13-DOUT)") (class "Default")
      (node (ref "APA13") (pin "2") (pinfunction "DOUT_2") (pintype "output"))
      (node (ref "APA20") (pin "4") (pinfunction "DIN_4") (pintype "input"))
    )
    (net (code "47") (name "Net-(APA14-DIN)") (class "Default")
      (node (ref "APA14") (pin "4") (pinfunction "DIN_4") (pintype "input"))
      (node (ref "APA15") (pin "2") (pinfunction "DOUT_2") (pintype "output"))
    )
    (net (code "48") (name "Net-(APA15-DIN)") (class "Default")
      (node (ref "APA15") (pin "4") (pinfunction "DIN_4") (pintype "input"))
      (node (ref "APA16") (pin "2") (pinfunction "DOUT_2") (pintype "output"))
    )
    (net (code "49") (name "Net-(APA17-DIN)") (class "Default")
      (node (ref "APA17") (pin "4") (pinfunction "DIN_4") (pintype "input"))
      (node (ref "APA18") (pin "2") (pinfunction "DOUT_2") (pintype "output"))
    )
    (net (code "50") (name "Net-(APA18-DIN)") (class "Default")
      (node (ref "APA18") (pin "4") (pinfunction "DIN_4") (pintype "input"))
      (node (ref "APA19") (pin "2") (pinfunction "DOUT_2") (pintype "output"))
    )
    (net (code "51") (name "Net-(APA19-DIN)") (class "Default")
      (node (ref "APA19") (pin "4") (pinfunction "DIN_4") (pintype "input"))
      (node (ref "APA20") (pin "2") (pinfunction "DOUT_2") (pintype "output"))
    )
    (net (code "52") (name "Net-(C19-Pad2)") (class "Default")
      (node (ref "C19") (pin "2") (pinfunction "2_2") (pintype "passive"))
      (node (ref "R6") (pin "2") (pinfunction "2_2") (pintype "passive"))
    )
    (net (code "53") (name "Net-(CHARGING_CIRCUT-PROG)") (class "Default")
      (node (ref "CHARGING_CIRCUT") (pin "5") (pinfunction "PROG_5") (pintype "bidirectional"))
      (node (ref "R3") (pin "2") (pinfunction "2_2") (pintype "passive"))
    )
    (net (code "54") (name "Net-(CHARGING_CIRCUT-STAT)") (class "Default")
      (node (ref "CHARGING_CIRCUT") (pin "1") (pinfunction "STAT_1") (pintype "bidirectional"))
      (node (ref "LED1") (pin "C") (pinfunction "C_C") (pintype "output"))
    )
    (net (code "55") (name "Net-(IC1-VCAP_1)") (class "Default")
      (node (ref "C17") (pin "1") (pinfunction "1_1") (pintype "passive"))
      (node (ref "IC1") (pin "30") (pinfunction "VCAP_1_30") (pintype "passive"))
    )
    (net (code "56") (name "Net-(LED1-PadA)") (class "Default")
      (node (ref "LED1") (pin "A") (pinfunction "A_A") (pintype "input"))
      (node (ref "R2") (pin "1") (pinfunction "1_1") (pintype "passive"))
    )
    (net (code "57") (name "Net-(VDO-EN)") (class "Default")
      (node (ref "P1") (pin "C") (pinfunction "C_C") (pintype "bidirectional"))
      (node (ref "VDO") (pin "1") (pinfunction "EN_1") (pintype "passive"))
    )
    (net (code "58") (name "Net-(VDO-VIN)") (class "Default")
      (node (ref "C3") (pin "2") (pinfunction "2_2") (pintype "passive"))
      (node (ref "ESP32PH") (pin "VCC") (pinfunction "VCC_VCC") (pintype "power_in"))
      (node (ref "LINK1") (pin "VCC") (pinfunction "VCC_VCC") (pintype "power_in"))
      (node (ref "P1") (pin "2") (pinfunction "2_2") (pintype "bidirectional"))
      (node (ref "RESETTABLE-FUSE") (pin "2") (pinfunction "2_2") (pintype "bidirectional"))
      (node (ref "VDO") (pin "6") (pinfunction "VIN_6") (pintype "passive"))
    )
    (net (code "59") (name "OSC_IN") (class "Default")
      (node (ref "C16") (pin "2") (pinfunction "2_2") (pintype "passive"))
      (node (ref "IC1") (pin "5") (pinfunction "PH0-OSC_IN_5") (pintype "passive"))
      (node (ref "R9") (pin "2") (pinfunction "2_2") (pintype "passive"))
      (node (ref "Y1") (pin "2") (pinfunction "2_2") (pintype "passive"))
    )
    (net (code "60") (name "OSC_OUT") (class "Default")
      (node (ref "C15") (pin "2") (pinfunction "2_2") (pintype "passive"))
      (node (ref "IC1") (pin "6") (pinfunction "PH1-OSC_OUT_6") (pintype "passive"))
      (node (ref "R9") (pin "1") (pinfunction "1_1") (pintype "passive"))
      (node (ref "Y1") (pin "1") (pinfunction "1_1") (pintype "passive"))
    )
    (net (code "61") (name "PA0") (class "Default")
      (node (ref "IC1") (pin "14") (pinfunction "PA0_14") (pintype "passive"))
      (node (ref "STM32-BREAKOUT") (pin "23") (pinfunction "23_23") (pintype "passive"))
    )
    (net (code "62") (name "PA1") (class "Default")
      (node (ref "IC1") (pin "15") (pinfunction "PA1_15") (pintype "passive"))
      (node (ref "STM32-BREAKOUT") (pin "25") (pinfunction "25_25") (pintype "passive"))
    )
    (net (code "63") (name "PA2") (class "Default")
      (node (ref "IC1") (pin "16") (pinfunction "PA2_16") (pintype "passive"))
      (node (ref "STM32-BREAKOUT") (pin "27") (pinfunction "27_27") (pintype "passive"))
    )
    (net (code "64") (name "PA3") (class "Default")
      (node (ref "IC1") (pin "17") (pinfunction "PA3_17") (pintype "passive"))
      (node (ref "STM32-BREAKOUT") (pin "29") (pinfunction "29_29") (pintype "passive"))
    )
    (net (code "65") (name "PA4") (class "Default")
      (node (ref "IC1") (pin "20") (pinfunction "PA4_20") (pintype "passive"))
      (node (ref "STM32-BREAKOUT") (pin "31") (pinfunction "31_31") (pintype "passive"))
    )
    (net (code "66") (name "PA5") (class "Default")
      (node (ref "IC1") (pin "21") (pinfunction "PA5_21") (pintype "passive"))
      (node (ref "STM32-BREAKOUT") (pin "33") (pinfunction "33_33") (pintype "passive"))
    )
    (net (code "67") (name "PA6") (class "Default")
      (node (ref "IC1") (pin "22") (pinfunction "PA6_22") (pintype "passive"))
      (node (ref "STM32-BREAKOUT") (pin "35") (pinfunction "35_35") (pintype "passive"))
    )
    (net (code "68") (name "PA7") (class "Default")
      (node (ref "IC1") (pin "23") (pinfunction "PA7_23") (pintype "passive"))
      (node (ref "STM32-BREAKOUT") (pin "37") (pinfunction "37_37") (pintype "passive"))
    )
    (net (code "69") (name "PA15") (class "Default")
      (node (ref "IC1") (pin "50") (pinfunction "PA15_50") (pintype "passive"))
      (node (ref "STM32-BREAKOUT") (pin "10") (pinfunction "10_10") (pintype "passive"))
    )
    (net (code "70") (name "PB0") (class "Default")
      (node (ref "IC1") (pin "26") (pinfunction "PB0_26") (pintype "passive"))
      (node (ref "STM32-BREAKOUT") (pin "38") (pinfunction "38_38") (pintype "passive"))
    )
    (net (code "71") (name "PB1") (class "Default")
      (node (ref "IC1") (pin "27") (pinfunction "PB1_27") (pintype "passive"))
      (node (ref "STM32-BREAKOUT") (pin "36") (pinfunction "36_36") (pintype "passive"))
    )
    (net (code "72") (name "PB3") (class "Default")
      (node (ref "IC1") (pin "55") (pinfunction "PB3_55") (pintype "passive"))
      (node (ref "M10") (pin "2") (pinfunction "2_2") (pintype "passive"))
    )
    (net (code "73") (name "PB4") (class "Default")
      (node (ref "IC1") (pin "56") (pinfunction "PB4_56") (pintype "passive"))
      (node (ref "M10") (pin "3") (pinfunction "3_3") (pintype "passive"))
    )
    (net (code "74") (name "PB5") (class "Default")
      (node (ref "IC1") (pin "57") (pinfunction "PB5_57") (pintype "passive"))
      (node (ref "M10") (pin "4") (pinfunction "4_4") (pintype "passive"))
    )
    (net (code "75") (name "PB6") (class "Default")
      (node (ref "IC1") (pin "58") (pinfunction "PB6_58") (pintype "passive"))
      (node (ref "M10") (pin "5") (pinfunction "5_5") (pintype "passive"))
    )
    (net (code "76") (name "PB7") (class "Default")
      (node (ref "IC1") (pin "59") (pinfunction "PB7_59") (pintype "passive"))
      (node (ref "M10") (pin "6") (pinfunction "6_6") (pintype "passive"))
    )
    (net (code "77") (name "PB8") (class "Default")
      (node (ref "IC1") (pin "61") (pinfunction "PB8_61") (pintype "passive"))
      (node (ref "M10") (pin "7") (pinfunction "7_7") (pintype "passive"))
    )
    (net (code "78") (name "PB9") (class "Default")
      (node (ref "IC1") (pin "62") (pinfunction "PB9_62") (pintype "passive"))
      (node (ref "M10") (pin "8") (pinfunction "8_8") (pintype "passive"))
    )
    (net (code "79") (name "PB13") (class "Default")
      (node (ref "IC1") (pin "34") (pinfunction "PB13_34") (pintype "passive"))
      (node (ref "STM32-BREAKOUT") (pin "21") (pinfunction "21_21") (pintype "passive"))
    )
    (net (code "80") (name "PB14") (class "Default")
      (node (ref "IC1") (pin "35") (pinfunction "PB14_35") (pintype "passive"))
      (node (ref "STM32-BREAKOUT") (pin "28") (pinfunction "28_28") (pintype "passive"))
    )
    (net (code "81") (name "PB15") (class "Default")
      (node (ref "IC1") (pin "36") (pinfunction "PB15_36") (pintype "passive"))
      (node (ref "STM32-BREAKOUT") (pin "26") (pinfunction "26_26") (pintype "passive"))
    )
    (net (code "82") (name "PC2") (class "Default")
      (node (ref "IC1") (pin "10") (pinfunction "PC2_10") (pintype "passive"))
      (node (ref "STM32-BREAKOUT") (pin "17") (pinfunction "17_17") (pintype "passive"))
    )
    (net (code "83") (name "PC6") (class "Default")
      (node (ref "IC1") (pin "37") (pinfunction "PC6_37") (pintype "passive"))
      (node (ref "STM32-BREAKOUT") (pin "24") (pinfunction "24_24") (pintype "passive"))
    )
    (net (code "84") (name "PC7") (class "Default")
      (node (ref "IC1") (pin "38") (pinfunction "PC7_38") (pintype "passive"))
      (node (ref "STM32-BREAKOUT") (pin "22") (pinfunction "22_22") (pintype "passive"))
    )
    (net (code "85") (name "PC8") (class "Default")
      (node (ref "IC1") (pin "39") (pinfunction "PC8_39") (pintype "passive"))
      (node (ref "STM32-BREAKOUT") (pin "20") (pinfunction "20_20") (pintype "passive"))
    )
    (net (code "86") (name "PC9") (class "Default")
      (node (ref "IC1") (pin "40") (pinfunction "PC9_40") (pintype "passive"))
      (node (ref "STM32-BREAKOUT") (pin "18") (pinfunction "18_18") (pintype "passive"))
    )
    (net (code "87") (name "PC10") (class "Default")
      (node (ref "IC1") (pin "51") (pinfunction "PC10_51") (pintype "passive"))
      (node (ref "STM32-BREAKOUT") (pin "8") (pinfunction "8_8") (pintype "passive"))
    )
    (net (code "88") (name "PC13") (class "Default")
      (node (ref "C19") (pin "1") (pinfunction "1_1") (pintype "passive"))
      (node (ref "IC1") (pin "2") (pinfunction "PC13_2") (pintype "passive"))
      (node (ref "R7") (pin "2") (pinfunction "2_2") (pintype "passive"))
      (node (ref "STM32-BREAKOUT") (pin "3") (pinfunction "3_3") (pintype "passive"))
      (node (ref "USERBUTTON") (pin "P$2") (pinfunction "C_P$2") (pintype "passive"))
    )
    (net (code "89") (name "PC14") (class "Default")
      (node (ref "IC1") (pin "3") (pinfunction "PC14-OSC32_IN_3") (pintype "passive"))
      (node (ref "STM32-BREAKOUT") (pin "5") (pinfunction "5_5") (pintype "passive"))
    )
    (net (code "90") (name "PC15") (class "Default")
      (node (ref "IC1") (pin "4") (pinfunction "PC15-OSC32_OUT_4") (pintype "passive"))
      (node (ref "STM32-BREAKOUT") (pin "7") (pinfunction "7_7") (pintype "passive"))
    )
    (net (code "91") (name "SD1") (class "Default")
      (node (ref "ESP-BREAKOUT") (pin "22") (pinfunction "22_22") (pintype "passive"))
      (node (ref "U1") (pin "22") (pinfunction "SD1_22") (pintype "bidirectional"))
    )
    (net (code "92") (name "SD2") (class "Default")
      (node (ref "ESP-BREAKOUT") (pin "17") (pinfunction "17_17") (pintype "passive"))
      (node (ref "U1") (pin "17") (pinfunction "SD2_17") (pintype "bidirectional"))
    )
    (net (code "93") (name "SD3") (class "Default")
      (node (ref "ESP-BREAKOUT") (pin "18") (pinfunction "18_18") (pintype "passive"))
      (node (ref "U1") (pin "18") (pinfunction "SD3_18") (pintype "bidirectional"))
    )
    (net (code "94") (name "SDO") (class "Default")
      (node (ref "ESP-BREAKOUT") (pin "21") (pinfunction "21_21") (pintype "passive"))
      (node (ref "U1") (pin "21") (pinfunction "SDO_21") (pintype "bidirectional"))
    )
    (net (code "95") (name "SD_CS") (class "Default")
      (node (ref "IC1") (pin "24") (pinfunction "PC4_24") (pintype "passive"))
      (node (ref "STM32-BREAKOUT") (pin "39") (pinfunction "39_39") (pintype "passive"))
      (node (ref "U$1") (pin "SD_CS") (pinfunction "SD_CS_SD_CS") (pintype "bidirectional"))
    )
    (net (code "96") (name "SENSOR_VN") (class "Default")
      (node (ref "ESP-BREAKOUT") (pin "5") (pinfunction "5_5") (pintype "passive"))
      (node (ref "U1") (pin "5") (pinfunction "SENSOR_VN_5") (pintype "bidirectional"))
    )
    (net (code "97") (name "SENSOR_VP") (class "Default")
      (node (ref "ESP-BREAKOUT") (pin "4") (pinfunction "4_4") (pintype "passive"))
      (node (ref "U1") (pin "4") (pinfunction "SENSOR_VP_4") (pintype "bidirectional"))
    )
    (net (code "98") (name "SPI2_LCD_MOSI") (class "Default")
      (node (ref "IC1") (pin "11") (pinfunction "PC3_11") (pintype "passive"))
      (node (ref "STM32-BREAKOUT") (pin "19") (pinfunction "19_19") (pintype "passive"))
      (node (ref "U$1") (pin "SDA") (pinfunction "SDA_SDA") (pintype "bidirectional"))
    )
    (net (code "99") (name "SPI2_LCD_SCK") (class "Default")
      (node (ref "IC1") (pin "29") (pinfunction "PB10_29") (pintype "passive"))
      (node (ref "STM32-BREAKOUT") (pin "32") (pinfunction "32_32") (pintype "passive"))
      (node (ref "U$1") (pin "SCK") (pinfunction "SCK_SCK") (pintype "bidirectional"))
    )
    (net (code "100") (name "SPI3_ESP_MISO") (class "Default")
      (node (ref "ESP-BREAKOUT") (pin "16") (pinfunction "16_16") (pintype "passive"))
      (node (ref "IC1") (pin "52") (pinfunction "PC11_52") (pintype "passive"))
      (node (ref "STM32-BREAKOUT") (pin "6") (pinfunction "6_6") (pintype "passive"))
      (node (ref "U$1") (pin "SD_MISO") (pinfunction "SD_MISO_SD_MISO") (pintype "bidirectional"))
      (node (ref "U1") (pin "16") (pinfunction "IO13_16") (pintype "bidirectional"))
    )
    (net (code "101") (name "SPI3_ESP_MOSI") (class "Default")
      (node (ref "ESP-BREAKOUT") (pin "14") (pinfunction "14_14") (pintype "passive"))
      (node (ref "IC1") (pin "53") (pinfunction "PC12_53") (pintype "passive"))
      (node (ref "STM32-BREAKOUT") (pin "4") (pinfunction "4_4") (pintype "passive"))
      (node (ref "U$1") (pin "SD_MOSI") (pinfunction "SD_MOSI_SD_MOSI") (pintype "bidirectional"))
      (node (ref "U1") (pin "14") (pinfunction "IO12_14") (pintype "bidirectional"))
    )
    (net (code "102") (name "SPI3_ESP_SCK") (class "Default")
      (node (ref "ESP-BREAKOUT") (pin "23") (pinfunction "23_23") (pintype "passive"))
      (node (ref "IC1") (pin "33") (pinfunction "PB12_33") (pintype "passive"))
      (node (ref "STM32-BREAKOUT") (pin "30") (pinfunction "30_30") (pintype "passive"))
      (node (ref "U$1") (pin "SD_SCK") (pinfunction "SD_SCK_SD_SCK") (pintype "bidirectional"))
      (node (ref "U1") (pin "23") (pinfunction "IO15_23") (pintype "bidirectional"))
    )
    (net (code "103") (name "SYS_JTCK_SWCLK") (class "Default")
      (node (ref "IC1") (pin "49") (pinfunction "PA14_49") (pintype "passive"))
      (node (ref "LINK1") (pin "SWDCLK") (pinfunction "SWDCLK_SWDCLK") (pintype "input"))
    )
    (net (code "104") (name "SYS_JTMS_SWDIO") (class "Default")
      (node (ref "IC1") (pin "46") (pinfunction "PA13_46") (pintype "passive"))
      (node (ref "LINK1") (pin "SWDIO") (pinfunction "SWDIO_SWDIO") (pintype "bidirectional"))
    )
    (net (code "105") (name "USART1_RX") (class "Default")
      (node (ref "IC1") (pin "43") (pinfunction "PA10_43") (pintype "passive"))
      (node (ref "STM32-BREAKOUT") (pin "12") (pinfunction "12_12") (pintype "passive"))
    )
    (net (code "106") (name "USART1_TX") (class "Default")
      (node (ref "IC1") (pin "42") (pinfunction "PA9_42") (pintype "passive"))
      (node (ref "STM32-BREAKOUT") (pin "14") (pinfunction "14_14") (pintype "passive"))
    )
    (net (code "107") (name "USB_DM") (class "Default")
      (node (ref "IC1") (pin "44") (pinfunction "PA11_44") (pintype "passive"))
      (node (ref "USB") (pin "D+") (pinfunction "D+_D+") (pintype "bidirectional"))
    )
    (net (code "108") (name "USB_DP") (class "Default")
      (node (ref "IC1") (pin "45") (pinfunction "PA12_45") (pintype "passive"))
      (node (ref "USB") (pin "D-") (pinfunction "D-_D-") (pintype "bidirectional"))
    )
    (net (code "109") (name "VCC") (class "Default")
      (node (ref "C10") (pin "1") (pinfunction "1_1") (pintype "passive"))
      (node (ref "C13") (pin "1") (pinfunction "1_1") (pintype "passive"))
      (node (ref "C4") (pin "1") (pinfunction "1_1") (pintype "passive"))
      (node (ref "C5") (pin "1") (pinfunction "1_1") (pintype "passive"))
      (node (ref "C6") (pin "1") (pinfunction "1_1") (pintype "passive"))
      (node (ref "C7") (pin "1") (pinfunction "1_1") (pintype "passive"))
      (node (ref "C8") (pin "1") (pinfunction "1_1") (pintype "passive"))
      (node (ref "C9") (pin "1") (pinfunction "1_1") (pintype "passive"))
      (node (ref "ESP-BREAKOUT") (pin "2") (pinfunction "2_2") (pintype "passive"))
      (node (ref "FB1") (pin "1") (pinfunction "1_1") (pintype "passive"))
      (node (ref "IC1") (pin "1") (pinfunction "VBAT_1") (pintype "passive"))
      (node (ref "IC1") (pin "19") (pinfunction "VDD(1)_19") (pintype "passive"))
      (node (ref "IC1") (pin "32") (pinfunction "VDD(2)_32") (pintype "passive"))
      (node (ref "IC1") (pin "48") (pinfunction "VDD(3)_48") (pintype "passive"))
      (node (ref "IC1") (pin "64") (pinfunction "VDD(4)_64") (pintype "passive"))
      (node (ref "M10") (pin "10") (pinfunction "10_10") (pintype "passive"))
      (node (ref "R1") (pin "2") (pinfunction "2_2") (pintype "passive"))
      (node (ref "R4") (pin "2") (pinfunction "2_2") (pintype "passive"))
      (node (ref "R7") (pin "1") (pinfunction "1_1") (pintype "passive"))
      (node (ref "R8") (pin "1") (pinfunction "1_1") (pintype "passive"))
      (node (ref "STM32-BREAKOUT") (pin "1") (pinfunction "1_1") (pintype "passive"))
      (node (ref "U$1") (pin "VCC") (pinfunction "VCC_VCC") (pintype "bidirectional"))
      (node (ref "U1") (pin "2") (pinfunction "3V3_2") (pintype "bidirectional"))
      (node (ref "VDO") (pin "4") (pinfunction "VOUT_4") (pintype "passive"))
    )
    (net (code "110") (name "VCC0") (class "Default")
      (node (ref "C2") (pin "1") (pinfunction "1_1") (pintype "passive"))
      (node (ref "CHARGING_CIRCUT") (pin "4") (pinfunction "VDD_4") (pintype "bidirectional"))
      (node (ref "R2") (pin "2") (pinfunction "2_2") (pintype "passive"))
      (node (ref "USB") (pin "+5V") (pinfunction "+5V_+5V") (pintype "bidirectional"))
    )
    (net (code "111") (name "VCC1") (class "Default")
      (node (ref "APA1") (pin "1") (pinfunction "VDD_1") (pintype "power_in"))
      (node (ref "APA10") (pin "1") (pinfunction "VDD_1") (pintype "power_in"))
      (node (ref "APA11") (pin "1") (pinfunction "VDD_1") (pintype "power_in"))
      (node (ref "APA12") (pin "1") (pinfunction "VDD_1") (pintype "power_in"))
      (node (ref "APA13") (pin "1") (pinfunction "VDD_1") (pintype "power_in"))
      (node (ref "APA14") (pin "1") (pinfunction "VDD_1") (pintype "power_in"))
      (node (ref "APA15") (pin "1") (pinfunction "VDD_1") (pintype "power_in"))
      (node (ref "APA16") (pin "1") (pinfunction "VDD_1") (pintype "power_in"))
      (node (ref "APA17") (pin "1") (pinfunction "VDD_1") (pintype "power_in"))
      (node (ref "APA18") (pin "1") (pinfunction "VDD_1") (pintype "power_in"))
      (node (ref "APA19") (pin "1") (pinfunction "VDD_1") (pintype "power_in"))
      (node (ref "APA2") (pin "1") (pinfunction "VDD_1") (pintype "power_in"))
      (node (ref "APA20") (pin "1") (pinfunction "VDD_1") (pintype "power_in"))
      (node (ref "APA3") (pin "1") (pinfunction "VDD_1") (pintype "power_in"))
      (node (ref "APA4") (pin "1") (pinfunction "VDD_1") (pintype "power_in"))
      (node (ref "APA5") (pin "1") (pinfunction "VDD_1") (pintype "power_in"))
      (node (ref "APA6") (pin "1") (pinfunction "VDD_1") (pintype "power_in"))
      (node (ref "APA7") (pin "1") (pinfunction "VDD_1") (pintype "power_in"))
      (node (ref "APA8") (pin "1") (pinfunction "VDD_1") (pintype "power_in"))
      (node (ref "APA9") (pin "1") (pinfunction "VDD_1") (pintype "power_in"))
      (node (ref "C1") (pin "1") (pinfunction "1_1") (pintype "passive"))
      (node (ref "C14") (pin "1") (pinfunction "1_1") (pintype "passive"))
      (node (ref "C29") (pin "1") (pinfunction "1_1") (pintype "passive"))
      (node (ref "C30") (pin "1") (pinfunction "1_1") (pintype "passive"))
      (node (ref "C31") (pin "1") (pinfunction "1_1") (pintype "passive"))
      (node (ref "C32") (pin "1") (pinfunction "1_1") (pintype "passive"))
      (node (ref "C33") (pin "1") (pinfunction "1_1") (pintype "passive"))
      (node (ref "C34") (pin "1") (pinfunction "1_1") (pintype "passive"))
      (node (ref "C35") (pin "1") (pinfunction "1_1") (pintype "passive"))
      (node (ref "C36") (pin "1") (pinfunction "1_1") (pintype "passive"))
      (node (ref "C37") (pin "1") (pinfunction "1_1") (pintype "passive"))
      (node (ref "C38") (pin "1") (pinfunction "1_1") (pintype "passive"))
      (node (ref "C39") (pin "1") (pinfunction "1_1") (pintype "passive"))
      (node (ref "C40") (pin "1") (pinfunction "1_1") (pintype "passive"))
      (node (ref "C41") (pin "1") (pinfunction "1_1") (pintype "passive"))
      (node (ref "C42") (pin "1") (pinfunction "1_1") (pintype "passive"))
      (node (ref "C43") (pin "1") (pinfunction "1_1") (pintype "passive"))
      (node (ref "C44") (pin "1") (pinfunction "1_1") (pintype "passive"))
      (node (ref "C45") (pin "1") (pinfunction "1_1") (pintype "passive"))
      (node (ref "C46") (pin "1") (pinfunction "1_1") (pintype "passive"))
      (node (ref "C47") (pin "1") (pinfunction "1_1") (pintype "passive"))
      (node (ref "CHARGING_CIRCUT") (pin "3") (pinfunction "VBAT_3") (pintype "bidirectional"))
      (node (ref "CN1") (pin "1") (pinfunction "2_1") (pintype "passive"))
      (node (ref "RESETTABLE-FUSE") (pin "1") (pinfunction "1_1") (pintype "bidirectional"))
    )
    (net (code "112") (name "VDDA") (class "Default")
      (node (ref "C11") (pin "1") (pinfunction "1_1") (pintype "passive"))
      (node (ref "C12") (pin "1") (pinfunction "1_1") (pintype "passive"))
      (node (ref "FB1") (pin "2") (pinfunction "2_2") (pintype "passive"))
      (node (ref "IC1") (pin "13") (pinfunction "VDDA/VREF+_13") (pintype "passive"))
    )
    (net (code "113") (name "unconnected-(APA17-DOUT-Pad2)") (class "Default")
      (node (ref "APA17") (pin "2") (pinfunction "DOUT_2") (pintype "output"))
    )
    (net (code "114") (name "unconnected-(ESP-BREAKOUT-Pad3)") (class "Default")
      (node (ref "ESP-BREAKOUT") (pin "3") (pinfunction "3_3") (pintype "passive"))
    )
    (net (code "115") (name "unconnected-(ESP-BREAKOUT-Pad32)") (class "Default")
      (node (ref "ESP-BREAKOUT") (pin "32") (pinfunction "32_32") (pintype "passive"))
    )
    (net (code "116") (name "unconnected-(ESP-BREAKOUT-Pad39)") (class "Default")
      (node (ref "ESP-BREAKOUT") (pin "39") (pinfunction "39_39") (pintype "passive"))
    )
    (net (code "117") (name "unconnected-(ESP-BREAKOUT-Pad40)") (class "Default")
      (node (ref "ESP-BREAKOUT") (pin "40") (pinfunction "40_40") (pintype "passive"))
    )
    (net (code "118") (name "unconnected-(U1-NC-Pad32)") (class "Default")
      (node (ref "U1") (pin "32") (pinfunction "NC_32") (pintype "bidirectional"))
    )
    (net (code "119") (name "unconnected-(USB-PadID)") (class "Default")
      (node (ref "USB") (pin "ID") (pinfunction "ID_ID") (pintype "bidirectional"))
    )
    (net (code "120") (name "unconnected-(VDO-NC-Pad5)") (class "Default")
      (node (ref "VDO") (pin "5") (pinfunction "NC_5") (pintype "no_connect"))
    )
    (net (code "121") (name "unconnected-(VDO-PG-Pad3)") (class "Default")
      (node (ref "VDO") (pin "3") (pinfunction "PG_3") (pintype "passive"))
    )
  )
)
